# PIC32MK.net
KiCad netlist of a schematic drawn in Altium Designer
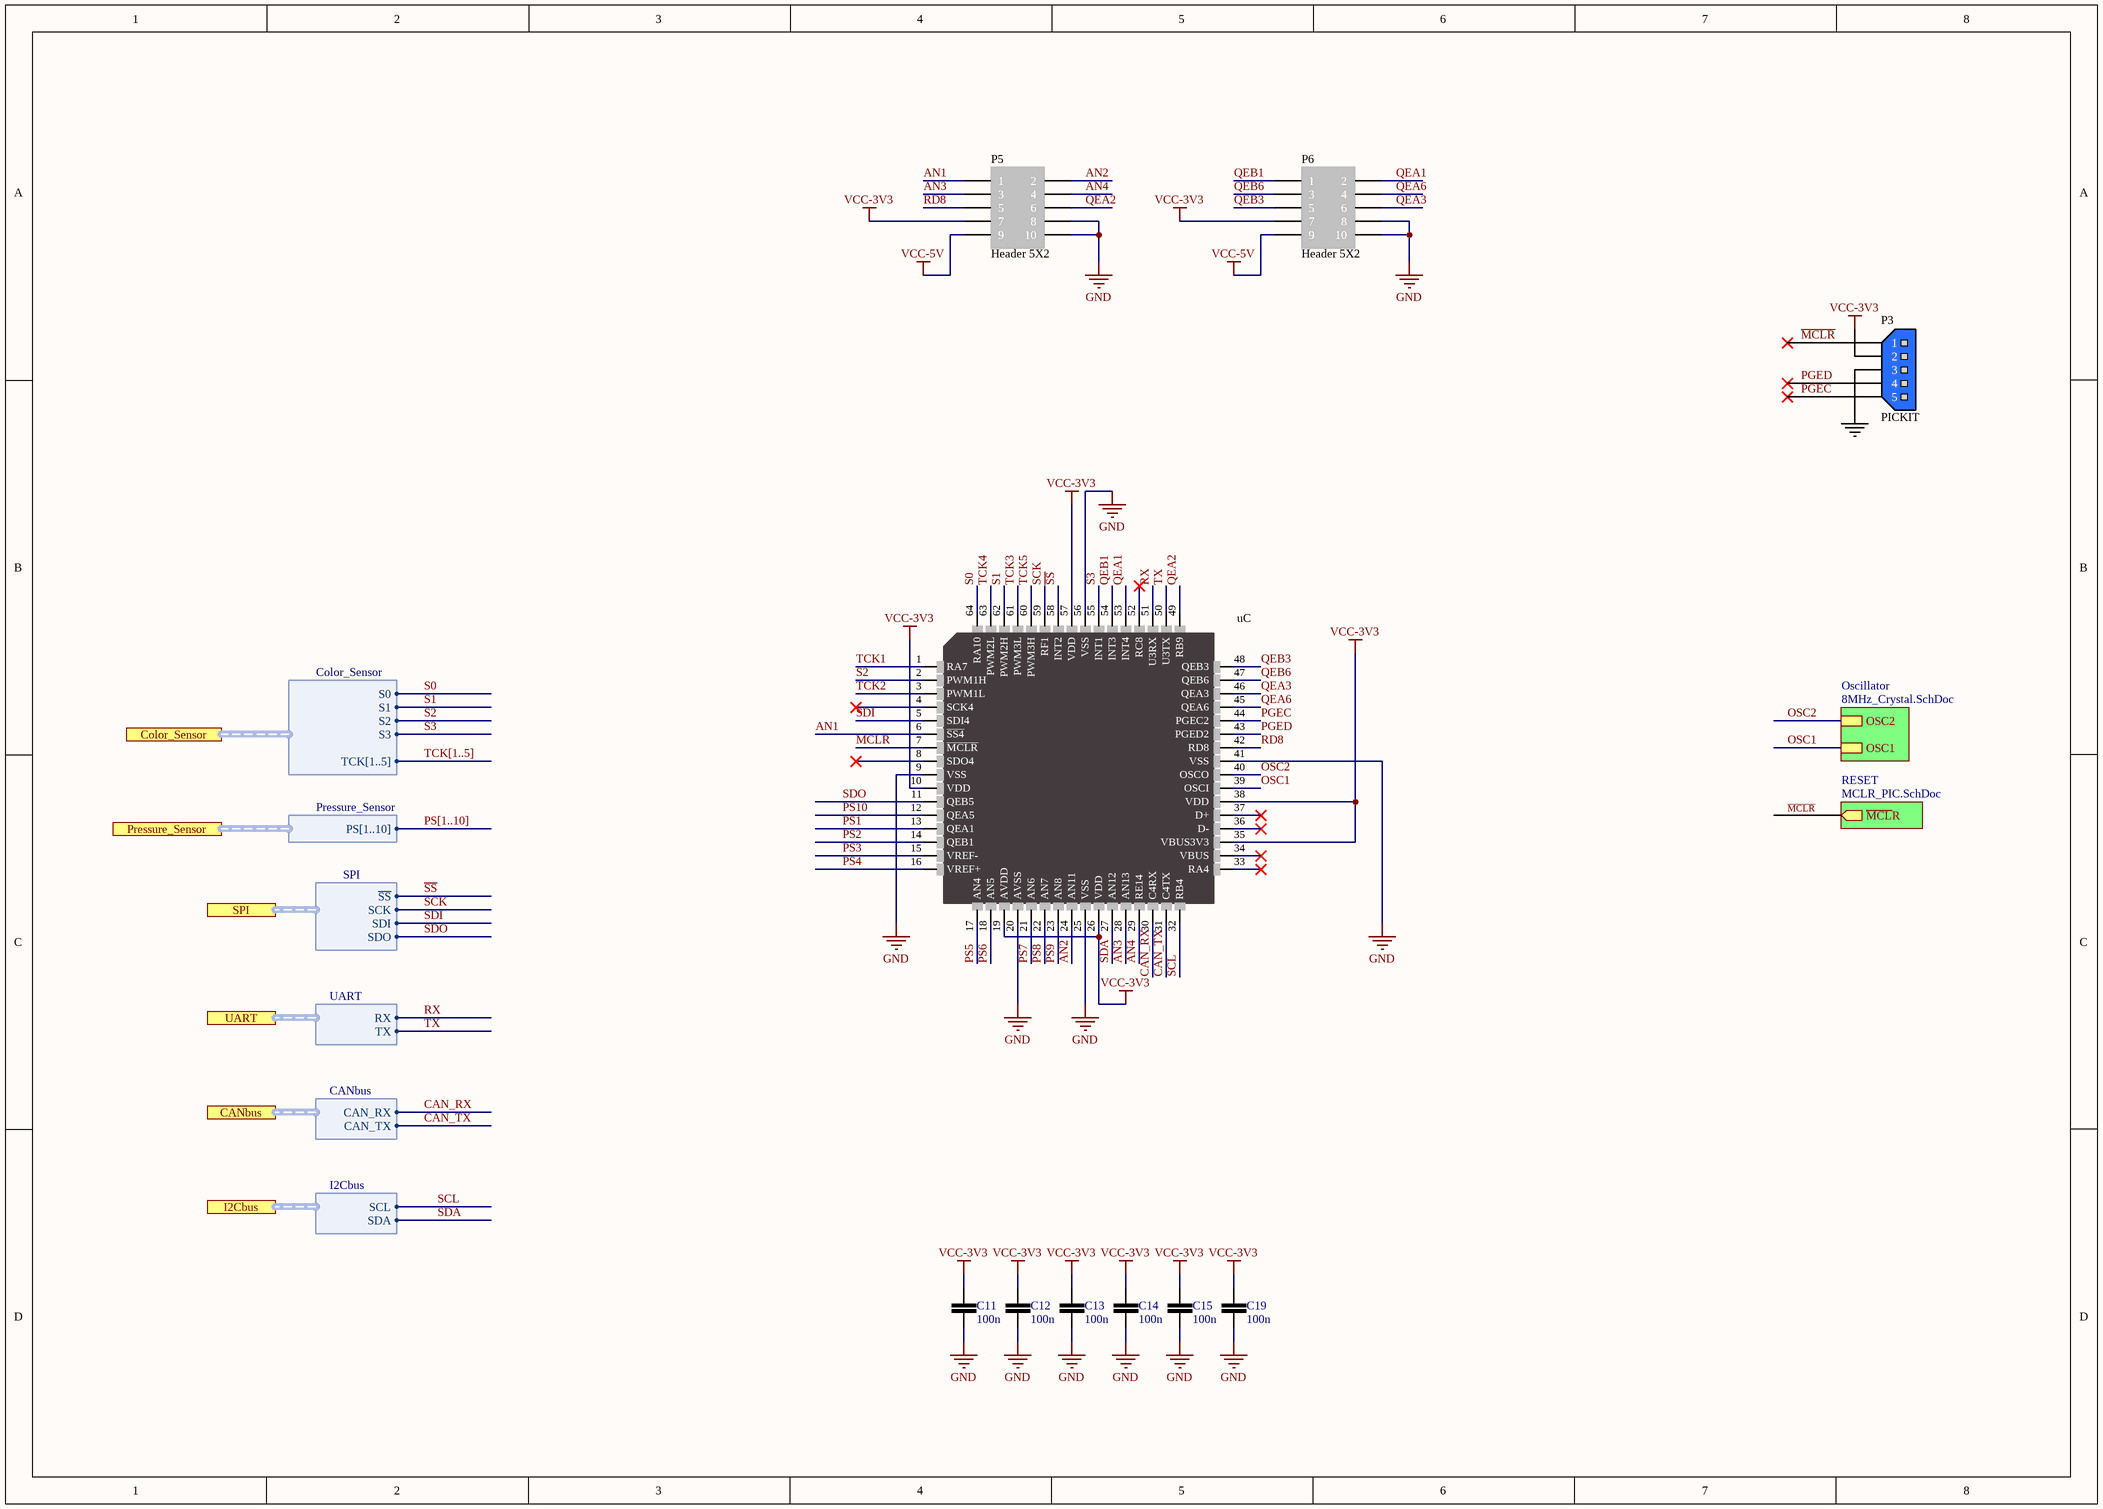
[diagram p0: PIC32MK.SchDoc]

(export (version "E")
  (design (tool "Eeschema 10.0.6"))
  (components
    (comp (ref "C11")
      (value "100n")
      (footprint "CER_0805")
      (fields
        (field (name "MANUFACTURER") "Yageo")
        (field (name "MANUFACTURER PART NUMBER") "CC0805KRX7R9BB104")
        (field (name "TOLERANCE") "10%")
      )
      (libsource (lib "capacitors") (part "0100000001868"))
    )
    (comp (ref "C12")
      (value "100n")
      (footprint "CER_0805")
      (fields
        (field (name "MANUFACTURER") "Yageo")
        (field (name "MANUFACTURER PART NUMBER") "CC0805KRX7R9BB104")
        (field (name "TOLERANCE") "10%")
      )
      (libsource (lib "capacitors") (part "0100000001868"))
    )
    (comp (ref "C13")
      (value "100n")
      (footprint "CER_0805")
      (fields
        (field (name "MANUFACTURER") "Yageo")
        (field (name "MANUFACTURER PART NUMBER") "CC0805KRX7R9BB104")
        (field (name "TOLERANCE") "10%")
      )
      (libsource (lib "capacitors") (part "0100000001868"))
    )
    (comp (ref "C14")
      (value "100n")
      (footprint "CER_0805")
      (fields
        (field (name "MANUFACTURER") "Yageo")
        (field (name "MANUFACTURER PART NUMBER") "CC0805KRX7R9BB104")
        (field (name "TOLERANCE") "10%")
      )
      (libsource (lib "capacitors") (part "0100000001868"))
    )
    (comp (ref "C15")
      (value "100n")
      (footprint "CER_0805")
      (fields
        (field (name "MANUFACTURER") "Yageo")
        (field (name "MANUFACTURER PART NUMBER") "CC0805KRX7R9BB104")
        (field (name "TOLERANCE") "10%")
      )
      (libsource (lib "capacitors") (part "0100000001868"))
    )
    (comp (ref "C19")
      (value "100n")
      (footprint "CER_0805")
      (fields
        (field (name "MANUFACTURER") "Yageo")
        (field (name "MANUFACTURER PART NUMBER") "CC0805KRX7R9BB104")
        (field (name "TOLERANCE") "10%")
      )
      (libsource (lib "capacitors") (part "0100000001868"))
    )
    (comp (ref "P3")
      (value "PICKIT")
      (footprint "TE CONNECTIVITY_5PIN_MALE")
      (description "BLUE_5PIN_CONECTOR")
      (fields (field (name "MANUFACTURER") "TE CONNECTIVITY / AMP"))
      (libsource (lib "Electro_Mechanical") (part "TE CONNECTIVITY_5PIN_MALE"))
    )
    (comp (ref "P5")
      (value "Header 5X2")
      (footprint "CONNECTOR_2X5")
      (description "Header, 5-Pin, Dual row")
      (fields (field (name "PUBLISHER") "Altium Limited"))
      (libsource (lib "Electro_Mechanical") (part "Header 5X2"))
    )
    (comp (ref "P6")
      (value "Header 5X2")
      (footprint "CONNECTOR_2X5")
      (description "Header, 5-Pin, Dual row")
      (fields (field (name "PUBLISHER") "Altium Limited"))
      (libsource (lib "Electro_Mechanical") (part "Header 5X2"))
    )
    (comp (ref "uC")
      (value "~")
      (footprint "TQFP-64-500um")
      (description "IC MCU 32BIT 1MB FLASH 64TQFP")
      (fields (field (name "MANUFACTURER PART NUMBER") "PIC32MK1024MCF064"))
      (libsource (lib "Integrated_circuits") (part "PIC32MK1024MCF064"))
    )
  )
  (nets
    (net (code "7") (name "/AN1") (class "Default")
      (node (ref "P5") (pin "1") (pinfunction "1_1") (pintype "passive"))
      (node (ref "uC") (pin "6") (pinfunction "~{SS4}_6") (pintype "passive"))
    )
    (net (code "8") (name "/AN2") (class "Default")
      (node (ref "P5") (pin "2") (pinfunction "2_2") (pintype "passive"))
      (node (ref "uC") (pin "24") (pinfunction "AN11_24") (pintype "passive"))
    )
    (net (code "9") (name "/AN3") (class "Default")
      (node (ref "P5") (pin "3") (pinfunction "3_3") (pintype "passive"))
      (node (ref "uC") (pin "28") (pinfunction "AN13_28") (pintype "passive"))
    )
    (net (code "10") (name "/AN4") (class "Default")
      (node (ref "P5") (pin "4") (pinfunction "4_4") (pintype "passive"))
      (node (ref "uC") (pin "29") (pinfunction "RE14_29") (pintype "passive"))
    )
    (net (code "11") (name "/CAN_RX") (class "Default")
      (node (ref "uC") (pin "30") (pinfunction "C4RX_30") (pintype "passive"))
    )
    (net (code "12") (name "/CAN_TX") (class "Default")
      (node (ref "uC") (pin "31") (pinfunction "C4TX_31") (pintype "passive"))
    )
    (net (code "14") (name "/OSC1") (class "Default")
      (node (ref "uC") (pin "39") (pinfunction "OSCI_39") (pintype "passive"))
    )
    (net (code "15") (name "/OSC2") (class "Default")
      (node (ref "uC") (pin "40") (pinfunction "OSCO_40") (pintype "passive"))
    )
    (net (code "16") (name "/PGEC") (class "Default")
      (node (ref "P3") (pin "5") (pinfunction "5_5") (pintype "passive"))
      (node (ref "uC") (pin "44") (pinfunction "PGEC2_44") (pintype "passive"))
    )
    (net (code "17") (name "/PGED") (class "Default")
      (node (ref "P3") (pin "4") (pinfunction "4_4") (pintype "passive"))
      (node (ref "uC") (pin "43") (pinfunction "PGED2_43") (pintype "passive"))
    )
    (net (code "18") (name "/PS1") (class "Default")
      (node (ref "uC") (pin "13") (pinfunction "QEA1_13") (pintype "passive"))
    )
    (net (code "19") (name "/PS2") (class "Default")
      (node (ref "uC") (pin "14") (pinfunction "QEB1_14") (pintype "passive"))
    )
    (net (code "20") (name "/PS3") (class "Default")
      (node (ref "uC") (pin "15") (pinfunction "VREF-_15") (pintype "passive"))
    )
    (net (code "21") (name "/PS4") (class "Default")
      (node (ref "uC") (pin "16") (pinfunction "VREF+_16") (pintype "passive"))
    )
    (net (code "22") (name "/PS5") (class "Default")
      (node (ref "uC") (pin "17") (pinfunction "AN4_17") (pintype "passive"))
    )
    (net (code "23") (name "/PS6") (class "Default")
      (node (ref "uC") (pin "18") (pinfunction "AN5_18") (pintype "passive"))
    )
    (net (code "24") (name "/PS7") (class "Default")
      (node (ref "uC") (pin "21") (pinfunction "AN6_21") (pintype "passive"))
    )
    (net (code "25") (name "/PS8") (class "Default")
      (node (ref "uC") (pin "22") (pinfunction "AN7_22") (pintype "passive"))
    )
    (net (code "26") (name "/PS9") (class "Default")
      (node (ref "uC") (pin "23") (pinfunction "AN8_23") (pintype "passive"))
    )
    (net (code "27") (name "/PS10") (class "Default")
      (node (ref "uC") (pin "12") (pinfunction "QEA5_12") (pintype "passive"))
    )
    (net (code "29") (name "/QEA1") (class "Default")
      (node (ref "P6") (pin "2") (pinfunction "2_2") (pintype "passive"))
      (node (ref "uC") (pin "53") (pinfunction "INT4_53") (pintype "passive"))
    )
    (net (code "30") (name "/QEA2") (class "Default")
      (node (ref "P5") (pin "6") (pinfunction "6_6") (pintype "passive"))
      (node (ref "uC") (pin "49") (pinfunction "RB9_49") (pintype "passive"))
    )
    (net (code "31") (name "/QEA3") (class "Default")
      (node (ref "P6") (pin "6") (pinfunction "6_6") (pintype "passive"))
      (node (ref "uC") (pin "46") (pinfunction "QEA3_46") (pintype "passive"))
    )
    (net (code "32") (name "/QEA6") (class "Default")
      (node (ref "P6") (pin "4") (pinfunction "4_4") (pintype "passive"))
      (node (ref "uC") (pin "45") (pinfunction "QEA6_45") (pintype "passive"))
    )
    (net (code "33") (name "/QEB1") (class "Default")
      (node (ref "P6") (pin "1") (pinfunction "1_1") (pintype "passive"))
      (node (ref "uC") (pin "54") (pinfunction "INT3_54") (pintype "passive"))
    )
    (net (code "34") (name "/QEB3") (class "Default")
      (node (ref "P6") (pin "5") (pinfunction "5_5") (pintype "passive"))
      (node (ref "uC") (pin "48") (pinfunction "QEB3_48") (pintype "passive"))
    )
    (net (code "35") (name "/QEB6") (class "Default")
      (node (ref "P6") (pin "3") (pinfunction "3_3") (pintype "passive"))
      (node (ref "uC") (pin "47") (pinfunction "QEB6_47") (pintype "passive"))
    )
    (net (code "36") (name "/RD8") (class "Default")
      (node (ref "P5") (pin "5") (pinfunction "5_5") (pintype "passive"))
      (node (ref "uC") (pin "42") (pinfunction "RD8_42") (pintype "passive"))
    )
    (net (code "37") (name "/RX") (class "Default")
      (node (ref "uC") (pin "51") (pinfunction "U3RX_51") (pintype "passive"))
    )
    (net (code "38") (name "/S0") (class "Default")
      (node (ref "uC") (pin "64") (pinfunction "RA10_64") (pintype "passive"))
    )
    (net (code "39") (name "/S1") (class "Default")
      (node (ref "uC") (pin "62") (pinfunction "PWM2H_62") (pintype "passive"))
    )
    (net (code "40") (name "/S2") (class "Default")
      (node (ref "uC") (pin "2") (pinfunction "PWM1H_2") (pintype "passive"))
    )
    (net (code "41") (name "/S3") (class "Default")
      (node (ref "uC") (pin "55") (pinfunction "INT1_55") (pintype "passive"))
    )
    (net (code "42") (name "/SCK") (class "Default")
      (node (ref "uC") (pin "59") (pinfunction "RF1_59") (pintype "passive"))
    )
    (net (code "43") (name "/SCL") (class "Default")
      (node (ref "uC") (pin "32") (pinfunction "RB4_32") (pintype "passive"))
    )
    (net (code "44") (name "/SDA") (class "Default")
      (node (ref "uC") (pin "27") (pinfunction "AN12_27") (pintype "passive"))
    )
    (net (code "45") (name "/SDI") (class "Default")
      (node (ref "uC") (pin "5") (pinfunction "SDI4_5") (pintype "passive"))
    )
    (net (code "46") (name "/SDO") (class "Default")
      (node (ref "uC") (pin "11") (pinfunction "QEB5_11") (pintype "passive"))
    )
    (net (code "47") (name "/TCK1") (class "Default")
      (node (ref "uC") (pin "1") (pinfunction "RA7_1") (pintype "passive"))
    )
    (net (code "48") (name "/TCK2") (class "Default")
      (node (ref "uC") (pin "3") (pinfunction "PWM1L_3") (pintype "passive"))
    )
    (net (code "49") (name "/TCK3") (class "Default")
      (node (ref "uC") (pin "61") (pinfunction "PWM3L_61") (pintype "passive"))
    )
    (net (code "50") (name "/TCK4") (class "Default")
      (node (ref "uC") (pin "63") (pinfunction "PWM2L_63") (pintype "passive"))
    )
    (net (code "51") (name "/TCK5") (class "Default")
      (node (ref "uC") (pin "60") (pinfunction "PWM3H_60") (pintype "passive"))
    )
    (net (code "52") (name "/TX") (class "Default")
      (node (ref "uC") (pin "50") (pinfunction "U3TX_50") (pintype "passive"))
    )
    (net (code "59") (name "/~{MCLR}") (class "Default")
      (node (ref "P3") (pin "1") (pinfunction "1_1") (pintype "passive"))
      (node (ref "uC") (pin "7") (pinfunction "~{MCLR}_7") (pintype "passive"))
    )
    (net (code "60") (name "/~{SS}") (class "Default")
      (node (ref "uC") (pin "58") (pinfunction "INT2_58") (pintype "passive"))
    )
    (net (code "61") (name "GND") (class "Default")
      (node (ref "C11") (pin "1") (pinfunction "1_1") (pintype "passive"))
      (node (ref "C12") (pin "1") (pinfunction "1_1") (pintype "passive"))
      (node (ref "C13") (pin "1") (pinfunction "1_1") (pintype "passive"))
      (node (ref "C14") (pin "1") (pinfunction "1_1") (pintype "passive"))
      (node (ref "C15") (pin "1") (pinfunction "1_1") (pintype "passive"))
      (node (ref "C19") (pin "1") (pinfunction "1_1") (pintype "passive"))
      (node (ref "P3") (pin "3") (pinfunction "3_3") (pintype "passive"))
      (node (ref "P5") (pin "10") (pinfunction "10_10") (pintype "passive"))
      (node (ref "P5") (pin "8") (pinfunction "8_8") (pintype "passive"))
      (node (ref "P6") (pin "10") (pinfunction "10_10") (pintype "passive"))
      (node (ref "P6") (pin "8") (pinfunction "8_8") (pintype "passive"))
      (node (ref "uC") (pin "20") (pinfunction "AVSS_20") (pintype "passive"))
      (node (ref "uC") (pin "25") (pinfunction "VSS_25") (pintype "passive"))
      (node (ref "uC") (pin "41") (pinfunction "VSS_41") (pintype "passive"))
      (node (ref "uC") (pin "56") (pinfunction "VSS_56") (pintype "passive"))
      (node (ref "uC") (pin "9") (pinfunction "VSS_9") (pintype "passive"))
    )
    (net (code "62") (name "VCC-3V3") (class "Default")
      (node (ref "C11") (pin "2") (pinfunction "2_2") (pintype "passive"))
      (node (ref "C12") (pin "2") (pinfunction "2_2") (pintype "passive"))
      (node (ref "C13") (pin "2") (pinfunction "2_2") (pintype "passive"))
      (node (ref "C14") (pin "2") (pinfunction "2_2") (pintype "passive"))
      (node (ref "C15") (pin "2") (pinfunction "2_2") (pintype "passive"))
      (node (ref "C19") (pin "2") (pinfunction "2_2") (pintype "passive"))
      (node (ref "P3") (pin "2") (pinfunction "2_2") (pintype "passive"))
      (node (ref "P5") (pin "7") (pinfunction "7_7") (pintype "passive"))
      (node (ref "P6") (pin "7") (pinfunction "7_7") (pintype "passive"))
      (node (ref "uC") (pin "10") (pinfunction "VDD_10") (pintype "passive"))
      (node (ref "uC") (pin "19") (pinfunction "AVDD_19") (pintype "passive"))
      (node (ref "uC") (pin "26") (pinfunction "VDD_26") (pintype "passive"))
      (node (ref "uC") (pin "35") (pinfunction "VBUS3V3_35") (pintype "passive"))
      (node (ref "uC") (pin "38") (pinfunction "VDD_38") (pintype "passive"))
      (node (ref "uC") (pin "57") (pinfunction "VDD_57") (pintype "passive"))
    )
    (net (code "63") (name "VCC-5V") (class "Default")
      (node (ref "P5") (pin "9") (pinfunction "9_9") (pintype "passive"))
      (node (ref "P6") (pin "9") (pinfunction "9_9") (pintype "passive"))
    )
    (net (code "64") (name "unconnected-(uC-D+-Pad37)") (class "Default")
      (node (ref "uC") (pin "37") (pinfunction "D+_37") (pintype "passive+no_connect"))
    )
    (net (code "65") (name "unconnected-(uC-D--Pad36)") (class "Default")
      (node (ref "uC") (pin "36") (pinfunction "D-_36") (pintype "passive+no_connect"))
    )
    (net (code "66") (name "unconnected-(uC-RA4-Pad33)") (class "Default")
      (node (ref "uC") (pin "33") (pinfunction "RA4_33") (pintype "passive+no_connect"))
    )
    (net (code "67") (name "unconnected-(uC-RC8-Pad52)") (class "Default")
      (node (ref "uC") (pin "52") (pinfunction "RC8_52") (pintype "passive+no_connect"))
    )
    (net (code "68") (name "unconnected-(uC-SCK4-Pad4)") (class "Default")
      (node (ref "uC") (pin "4") (pinfunction "SCK4_4") (pintype "passive+no_connect"))
    )
    (net (code "69") (name "unconnected-(uC-SDO4-Pad8)") (class "Default")
      (node (ref "uC") (pin "8") (pinfunction "SDO4_8") (pintype "passive+no_connect"))
    )
    (net (code "70") (name "unconnected-(uC-VBUS-Pad34)") (class "Default")
      (node (ref "uC") (pin "34") (pinfunction "VBUS_34") (pintype "passive+no_connect"))
    )
  )
)
